# POWER_MS.net
KiCad netlist of a schematic drawn in Altium Designer
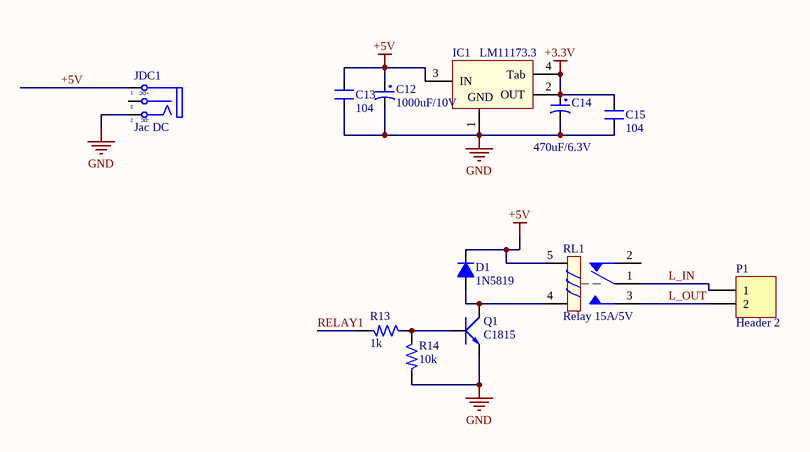
[diagram p0: POWER_MS.SchDoc]

(export (version "E")
  (design (tool "Eeschema 10.0.6"))
  (components
    (comp (ref "C12")
      (value "1000uF/10V")
      (footprint "CP1.5/3.4")
      (description "Cap P  0,1uF < 22uF , 16 - 50V")
      (libsource (lib "nl") (part "CP1"))
    )
    (comp (ref "C13")
      (value "104")
      (footprint "C0603")
      (description "Cremic For Xtal 1pF => 100pF")
      (libsource (lib "nl") (part "CAP"))
    )
    (comp (ref "C14")
      (value "470uF/6.3V")
      (footprint "CP1/2")
      (description "Cap P  0,1uF < 22uF , 16 - 50V")
      (libsource (lib "nl") (part "CP1"))
    )
    (comp (ref "C15")
      (value "104")
      (footprint "C0603")
      (description "Cremic For Xtal 1pF => 100pF")
      (libsource (lib "nl") (part "CAP"))
    )
    (comp (ref "D1")
      (value "1N5819")
      (footprint "DO-214AC")
      (description "Diode 1A")
      (libsource (lib "PCB_MS") (part "D1A"))
    )
    (comp (ref "IC1")
      (value "LM11173.3")
      (footprint "SOT223-4N")
      (description "3v3")
      (libsource (lib "syhaunguyen") (part "LM1117"))
    )
    (comp (ref "JDC1")
      (value "Jac DC")
      (footprint "DC-IN")
      (description "Jac DC input")
      (libsource (lib "syhaunguyen") (part "DCIN"))
    )
    (comp (ref "P1")
      (value "Header 2")
      (footprint "HDR1X2")
      (description "Header, 2-Pin")
      (fields (field (name "PUBLISHER") "Altium Limited"))
      (libsource (lib "Miscellaneous Connectors") (part "Header 2"))
    )
    (comp (ref "Q1")
      (value "C1815")
      (footprint "SOT23B")
      (description "NPN 600mW, ECB")
      (libsource (lib "syhaunguyen") (part "C1815"))
    )
    (comp (ref "R13")
      (value "1k")
      (footprint "R0603")
      (description "Resistor 1/4W")
      (libsource (lib "nl") (part "R"))
    )
    (comp (ref "R14")
      (value "10k")
      (footprint "R0603")
      (description "Resistor 1/4W")
      (libsource (lib "nl") (part "R"))
    )
    (comp (ref "RL1")
      (value "Relay 15A/5V")
      (footprint "HF32F-JZC-32F")
      (description "Relay SPDT,10A - 12VDC 5 Pin")
      (libsource (lib "syhaunguyen") (part "Relay 1"))
    )
  )
  (nets
    (net (code "1") (name "+3.3V") (class "Default")
      (node (ref "C14") (pin "1") (pinfunction "1_1") (pintype "passive"))
      (node (ref "C15") (pin "2") (pinfunction "2_2") (pintype "passive"))
      (node (ref "IC1") (pin "2") (pinfunction "OUT_2") (pintype "passive"))
      (node (ref "IC1") (pin "4") (pinfunction "Tab_4") (pintype "passive"))
    )
    (net (code "2") (name "+5V") (class "Default")
      (node (ref "C12") (pin "1") (pinfunction "1_1") (pintype "passive"))
      (node (ref "C13") (pin "2") (pinfunction "2_2") (pintype "passive"))
      (node (ref "D1") (pin "2") (pinfunction "K_2") (pintype "passive"))
      (node (ref "IC1") (pin "3") (pinfunction "IN_3") (pintype "passive"))
      (node (ref "JDC1") (pin "1") (pinfunction "T_1") (pintype "passive"))
      (node (ref "RL1") (pin "5") (pinfunction "5_5") (pintype "passive"))
    )
    (net (code "3") (name "/L_IN") (class "Default")
      (node (ref "P1") (pin "1") (pinfunction "1_1") (pintype "passive"))
      (node (ref "RL1") (pin "1") (pinfunction "1_1") (pintype "passive"))
    )
    (net (code "4") (name "/L_OUT") (class "Default")
      (node (ref "P1") (pin "2") (pinfunction "2_2") (pintype "passive"))
      (node (ref "RL1") (pin "3") (pinfunction "3_3") (pintype "passive"))
    )
    (net (code "5") (name "/RELAY1") (class "Default")
      (node (ref "R13") (pin "2") (pinfunction "2_2") (pintype "passive"))
    )
    (net (code "6") (name "GND") (class "Default")
      (node (ref "C12") (pin "2") (pinfunction "2_2") (pintype "passive"))
      (node (ref "C13") (pin "1") (pinfunction "1_1") (pintype "passive"))
      (node (ref "C14") (pin "2") (pinfunction "2_2") (pintype "passive"))
      (node (ref "C15") (pin "1") (pinfunction "1_1") (pintype "passive"))
      (node (ref "IC1") (pin "1") (pinfunction "ADJ/G_1") (pintype "passive"))
      (node (ref "JDC1") (pin "2") (pinfunction "TN_2") (pintype "passive"))
      (node (ref "Q1") (pin "1") (pinfunction "E_1") (pintype "passive"))
      (node (ref "R14") (pin "2") (pinfunction "2_2") (pintype "passive"))
    )
    (net (code "7") (name "Net-(D1-A)") (class "Default")
      (node (ref "D1") (pin "1") (pinfunction "A_1") (pintype "passive"))
      (node (ref "Q1") (pin "2") (pinfunction "C_2") (pintype "passive"))
      (node (ref "RL1") (pin "4") (pinfunction "4_4") (pintype "passive"))
    )
    (net (code "8") (name "Net-(Q1-B)") (class "Default")
      (node (ref "Q1") (pin "3") (pinfunction "B_3") (pintype "passive"))
      (node (ref "R13") (pin "1") (pinfunction "1_1") (pintype "passive"))
      (node (ref "R14") (pin "1") (pinfunction "1_1") (pintype "passive"))
    )
    (net (code "9") (name "unconnected-(JDC1-S-Pad3)") (class "Default")
      (node (ref "JDC1") (pin "3") (pinfunction "S_3") (pintype "power_in"))
    )
    (net (code "10") (name "unconnected-(RL1-Pad2)") (class "Default")
      (node (ref "RL1") (pin "2") (pinfunction "2_2") (pintype "passive"))
    )
  )
)
